# seedrum_ph_v1.net
KiCad netlist of a schematic drawn in EasyEDA
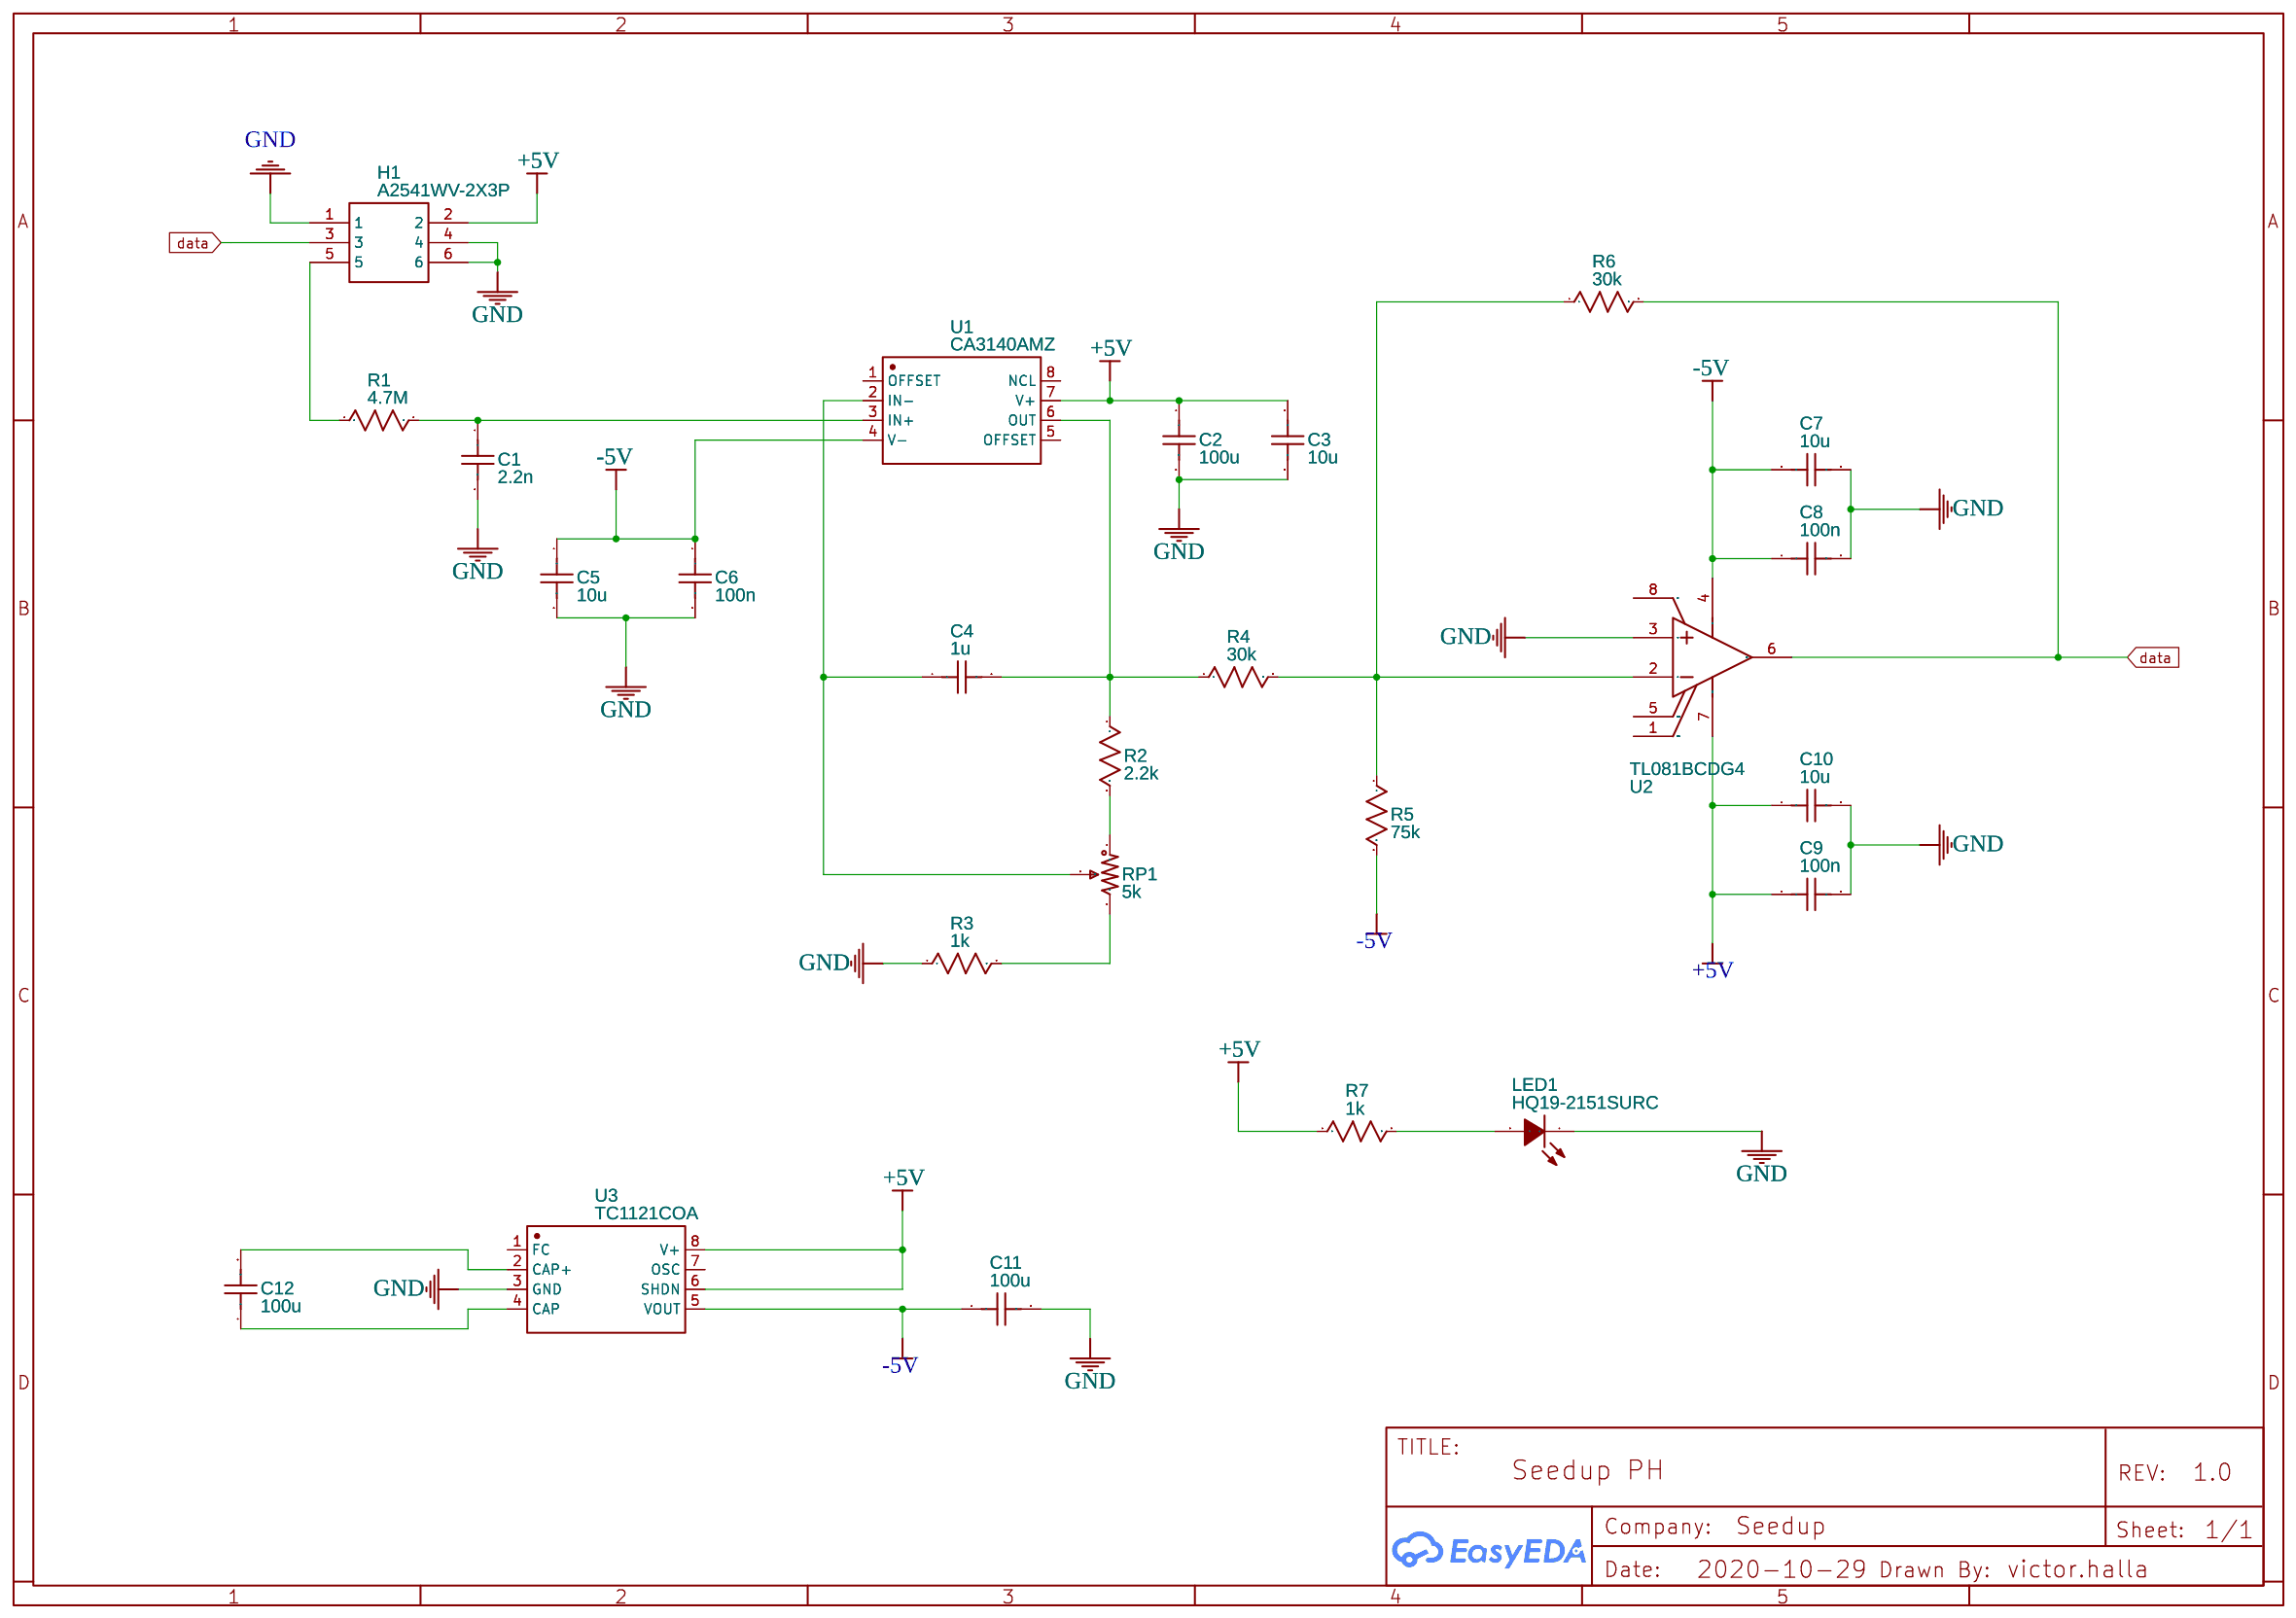
[diagram p0: schematic sheet]

(export (version "E")
  (design (tool "Eeschema 10.0.6"))
  (components
    (comp (ref "C1") (value "2.2n") (libsource (lib "") (part "C_0603_US_1")))
    (comp (ref "C2") (value "100u") (libsource (lib "") (part "C_0603_US_1")))
    (comp (ref "C3") (value "10u") (libsource (lib "") (part "C_0603_US_1")))
    (comp (ref "C4") (value "1u") (libsource (lib "") (part "C_0603_US")))
    (comp (ref "C5") (value "10u") (libsource (lib "") (part "C_0603_US_1")))
    (comp (ref "C6") (value "100n") (libsource (lib "") (part "C_0603_US_1")))
    (comp (ref "C7") (value "10u") (libsource (lib "") (part "C_0603_US")))
    (comp (ref "C8") (value "100n") (libsource (lib "") (part "C_0603_US")))
    (comp (ref "C9") (value "100n") (libsource (lib "") (part "C_0603_US")))
    (comp (ref "C10") (value "10u") (libsource (lib "") (part "C_0603_US")))
    (comp (ref "C11") (value "100u") (libsource (lib "") (part "C_0603_US")))
    (comp (ref "C12") (value "100u") (libsource (lib "") (part "C_0603_US_2")))
    (comp (ref "H1")
      (value "A2541WV-2X3P")
      (fields
        (field (name "BOM_Manufacturer Part") "A2541WV-2x3P")
        (field (name "BOM_Supplier Part") "C225518")
      )
      (libsource (lib "") (part "A2541WV-2X3P"))
    )
    (comp (ref "LED1")
      (value "HQ19-2151SURC")
      (fields (field (name "BOM_Supplier Part") "C258842"))
      (libsource (lib "") (part "HQ19-2151SURC"))
    )
    (comp (ref "R1") (value "4.7M") (libsource (lib "") (part "R_0603_US_1")))
    (comp (ref "R2") (value "2.2k") (libsource (lib "") (part "R_0603_US")))
    (comp (ref "R3") (value "1k") (libsource (lib "") (part "R_0603_US_1")))
    (comp (ref "R4") (value "30k") (libsource (lib "") (part "R_0603_US_1")))
    (comp (ref "R5") (value "75k") (libsource (lib "") (part "R_0603_US")))
    (comp (ref "R6") (value "30k") (libsource (lib "") (part "R_0603_US_1")))
    (comp (ref "R7") (value "1k") (libsource (lib "") (part "R_0603_US_1")))
    (comp (ref "RP1") (value "5k") (libsource (lib "") (part "R_3386P_US")))
    (comp (ref "U1")
      (value "CA3140AMZ")
      (fields (field (name "BOM_Manufacturer Part") "AD8052ARZ") (field (name "BOM_Supplier Part") "C86654"))
      (libsource (lib "") (part "CA3140AMZ"))
    )
    (comp (ref "U2") (value "TL081BCDG4") (libsource (lib "") (part "TL081BCDG4")))
    (comp (ref "U3") (value "TC1121COA") (libsource (lib "") (part "TC1121COA")))
  )
  (nets
    (net (code "1") (name "+5V") (class "Default")
      (node (ref "C10") (pin "1") (pinfunction "1_1") (pintype "unspecified"))
      (node (ref "C2") (pin "1") (pinfunction "1_1") (pintype "unspecified"))
      (node (ref "C3") (pin "1") (pinfunction "1_1") (pintype "unspecified"))
      (node (ref "C9") (pin "1") (pinfunction "1_1") (pintype "unspecified"))
      (node (ref "H1") (pin "2") (pinfunction "2_2") (pintype "unspecified"))
      (node (ref "R7") (pin "1") (pinfunction "1_1") (pintype "unspecified"))
      (node (ref "U1") (pin "7") (pinfunction "V+_7") (pintype "unspecified"))
      (node (ref "U2") (pin "7") (pinfunction "VCC+_7") (pintype "passive"))
      (node (ref "U3") (pin "6") (pinfunction "SHDN_6") (pintype "unspecified"))
      (node (ref "U3") (pin "8") (pinfunction "V+_8") (pintype "unspecified"))
    )
    (net (code "2") (name "-5V") (class "Default")
      (node (ref "C11") (pin "1") (pinfunction "1_1") (pintype "unspecified"))
      (node (ref "C5") (pin "1") (pinfunction "1_1") (pintype "unspecified"))
      (node (ref "C6") (pin "1") (pinfunction "1_1") (pintype "unspecified"))
      (node (ref "C7") (pin "1") (pinfunction "1_1") (pintype "unspecified"))
      (node (ref "C8") (pin "1") (pinfunction "1_1") (pintype "unspecified"))
      (node (ref "R5") (pin "2") (pinfunction "2_2") (pintype "unspecified"))
      (node (ref "U1") (pin "4") (pinfunction "V-_4") (pintype "unspecified"))
      (node (ref "U2") (pin "4") (pinfunction "VCC-_4") (pintype "passive"))
      (node (ref "U3") (pin "5") (pinfunction "VOUT_5") (pintype "unspecified"))
    )
    (net (code "3") (name "GND") (class "Default")
      (node (ref "C1") (pin "2") (pinfunction "2_2") (pintype "unspecified"))
      (node (ref "C10") (pin "2") (pinfunction "2_2") (pintype "unspecified"))
      (node (ref "C11") (pin "2") (pinfunction "2_2") (pintype "unspecified"))
      (node (ref "C2") (pin "2") (pinfunction "2_2") (pintype "unspecified"))
      (node (ref "C3") (pin "2") (pinfunction "2_2") (pintype "unspecified"))
      (node (ref "C5") (pin "2") (pinfunction "2_2") (pintype "unspecified"))
      (node (ref "C6") (pin "2") (pinfunction "2_2") (pintype "unspecified"))
      (node (ref "C7") (pin "2") (pinfunction "2_2") (pintype "unspecified"))
      (node (ref "C8") (pin "2") (pinfunction "2_2") (pintype "unspecified"))
      (node (ref "C9") (pin "2") (pinfunction "2_2") (pintype "unspecified"))
      (node (ref "H1") (pin "1") (pinfunction "1_1") (pintype "unspecified"))
      (node (ref "H1") (pin "4") (pinfunction "4_4") (pintype "unspecified"))
      (node (ref "H1") (pin "6") (pinfunction "6_6") (pintype "unspecified"))
      (node (ref "LED1") (pin "1") (pinfunction "K_1") (pintype "unspecified"))
      (node (ref "R3") (pin "1") (pinfunction "1_1") (pintype "unspecified"))
      (node (ref "U2") (pin "3") (pinfunction "IN+_3") (pintype "unspecified"))
      (node (ref "U3") (pin "3") (pinfunction "GND_3") (pintype "unspecified"))
    )
    (net (code "4") (name "Net-(H1-Pad5)") (class "Default")
      (node (ref "H1") (pin "5") (pinfunction "5_5") (pintype "unspecified"))
      (node (ref "R1") (pin "1") (pinfunction "1_1") (pintype "unspecified"))
    )
    (net (code "5") (name "Net-(LED1-A)") (class "Default")
      (node (ref "LED1") (pin "2") (pinfunction "A_2") (pintype "unspecified"))
      (node (ref "R7") (pin "2") (pinfunction "2_2") (pintype "unspecified"))
    )
    (net (code "6") (name "Net-(R2-Pad2)") (class "Default")
      (node (ref "R2") (pin "2") (pinfunction "2_2") (pintype "unspecified"))
      (node (ref "RP1") (pin "1") (pinfunction "1_1") (pintype "unspecified"))
    )
    (net (code "7") (name "Net-(R3-Pad2)") (class "Default")
      (node (ref "R3") (pin "2") (pinfunction "2_2") (pintype "unspecified"))
      (node (ref "RP1") (pin "3") (pinfunction "3_3") (pintype "unspecified"))
    )
    (net (code "8") (name "Net-(U1-IN+)") (class "Default")
      (node (ref "C1") (pin "1") (pinfunction "1_1") (pintype "unspecified"))
      (node (ref "R1") (pin "2") (pinfunction "2_2") (pintype "unspecified"))
      (node (ref "U1") (pin "3") (pinfunction "IN+_3") (pintype "unspecified"))
    )
    (net (code "9") (name "Net-(U1-IN-)") (class "Default")
      (node (ref "C4") (pin "1") (pinfunction "1_1") (pintype "unspecified"))
      (node (ref "RP1") (pin "2") (pinfunction "2_2") (pintype "unspecified"))
      (node (ref "U1") (pin "2") (pinfunction "IN-_2") (pintype "unspecified"))
    )
    (net (code "10") (name "Net-(U1-OUT)") (class "Default")
      (node (ref "C4") (pin "2") (pinfunction "2_2") (pintype "unspecified"))
      (node (ref "R2") (pin "1") (pinfunction "1_1") (pintype "unspecified"))
      (node (ref "R4") (pin "1") (pinfunction "1_1") (pintype "unspecified"))
      (node (ref "U1") (pin "6") (pinfunction "OUT_6") (pintype "unspecified"))
    )
    (net (code "11") (name "Net-(U2-IN-)") (class "Default")
      (node (ref "R4") (pin "2") (pinfunction "2_2") (pintype "unspecified"))
      (node (ref "R5") (pin "1") (pinfunction "1_1") (pintype "unspecified"))
      (node (ref "R6") (pin "1") (pinfunction "1_1") (pintype "unspecified"))
      (node (ref "U2") (pin "2") (pinfunction "IN-_2") (pintype "unspecified"))
    )
    (net (code "12") (name "Net-(U3-CAP)") (class "Default")
      (node (ref "C12") (pin "1") (pinfunction "1_1") (pintype "unspecified"))
      (node (ref "U3") (pin "4") (pinfunction "CAP_4") (pintype "unspecified"))
    )
    (net (code "13") (name "Net-(U3-CAP+)") (class "Default")
      (node (ref "C12") (pin "2") (pinfunction "2_2") (pintype "unspecified"))
      (node (ref "U3") (pin "2") (pinfunction "CAP+_2") (pintype "unspecified"))
    )
    (net (code "14") (name "data") (class "Default")
      (node (ref "H1") (pin "3") (pinfunction "3_3") (pintype "unspecified"))
      (node (ref "R6") (pin "2") (pinfunction "2_2") (pintype "unspecified"))
      (node (ref "U2") (pin "6") (pinfunction "OUT_6") (pintype "output"))
    )
    (net (code "15") (name "unconnected-(U1-NCL-Pad8)") (class "Default")
      (node (ref "U1") (pin "8") (pinfunction "NCL_8") (pintype "unspecified"))
    )
    (net (code "16") (name "unconnected-(U1-OFFSET-Pad1)") (class "Default")
      (node (ref "U1") (pin "1") (pinfunction "OFFSET_1") (pintype "unspecified"))
    )
    (net (code "17") (name "unconnected-(U1-OFFSET-Pad5)") (class "Default")
      (node (ref "U1") (pin "5") (pinfunction "OFFSET_5") (pintype "unspecified"))
    )
    (net (code "18") (name "unconnected-(U2-NC-Pad8)") (class "Default")
      (node (ref "U2") (pin "8") (pinfunction "NC_8") (pintype "unspecified"))
    )
    (net (code "19") (name "unconnected-(U2-OFFSET_N1-Pad1)") (class "Default")
      (node (ref "U2") (pin "1") (pinfunction "OFFSET_N1_1") (pintype "unspecified"))
    )
    (net (code "20") (name "unconnected-(U2-OFFSET_N2-Pad5)") (class "Default")
      (node (ref "U2") (pin "5") (pinfunction "OFFSET_N2_5") (pintype "unspecified"))
    )
    (net (code "21") (name "unconnected-(U3-FC-Pad1)") (class "Default")
      (node (ref "U3") (pin "1") (pinfunction "FC_1") (pintype "unspecified"))
    )
    (net (code "22") (name "unconnected-(U3-OSC-Pad7)") (class "Default")
      (node (ref "U3") (pin "7") (pinfunction "OSC_7") (pintype "unspecified"))
    )
  )
)
